# MiniSumoMotors.net
KiCad netlist of a schematic drawn in EAGLE
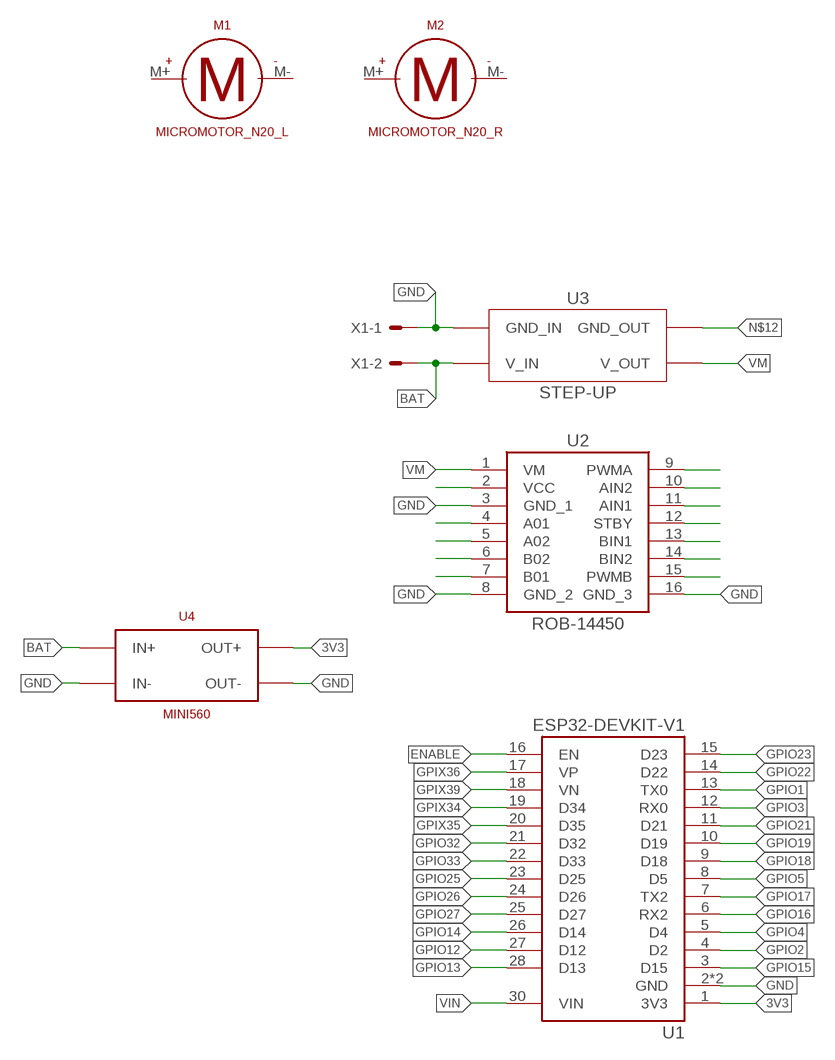
[diagram p0: schematic, sheet 1]

(export (version "E")
  (design (tool "Eeschema 10.0.6"))
  (components
    (comp (ref "M1")
      (value "MICROMOTOR_N20_L")
      (footprint "eagle-import:MICROMOTOR-L")
      (libsource (lib "eagle-import") (part "MICROMOTOR_N20_L"))
    )
    (comp (ref "M2")
      (value "MICROMOTOR_N20_R")
      (footprint "eagle-import:MICROMOTOR-R")
      (libsource (lib "eagle-import") (part "MICROMOTOR_N20_R"))
    )
    (comp (ref "U1")
      (value "ESP32-DEVKIT-V1")
      (footprint "eagle-import:MODULE_ESP32_DEVKIT_V1")
      (fields (field (name "MF") "Do it"))
      (libsource (lib "eagle-import") (part "ESP32-DEVKIT-V1"))
    )
    (comp (ref "U2")
      (value "ROB-14450")
      (footprint "eagle-import:ROB14450")
      (fields (field (name "MOUSER_PART_NUMBER") "474-ROB-14450"))
      (libsource (lib "eagle-import") (part "ROB-14450"))
    )
    (comp (ref "U3")
      (value "STEP-UP")
      (footprint "eagle-import:STEP-UP")
      (libsource (lib "eagle-import") (part "STEP-UP"))
    )
    (comp (ref "U4")
      (value "MINI560")
      (footprint "eagle-import:MINI560")
      (libsource (lib "eagle-import") (part "MINI560"))
    )
    (comp (ref "X1")
      (value "22-23-2021")
      (footprint "eagle-import:22-23-2021")
      (fields (field (name "MF") "MOLEX"))
      (libsource (lib "eagle-import") (part "22-23-2021"))
    )
  )
  (nets
    (net (code "1") (name "3V3") (class "Default")
      (node (ref "U1") (pin "1") (pinfunction "3V3_1") (pintype "output"))
      (node (ref "U4") (pin "P$11") (pinfunction "OUT+_P$11") (pintype "bidirectional"))
      (node (ref "U4") (pin "P$12") (pinfunction "OUT+_P$12") (pintype "bidirectional"))
      (node (ref "U4") (pin "P$15") (pinfunction "OUT+_P$15") (pintype "bidirectional"))
      (node (ref "U4") (pin "P$16") (pinfunction "OUT+_P$16") (pintype "bidirectional"))
    )
    (net (code "2") (name "BAT") (class "Default")
      (node (ref "U3") (pin "V_IN") (pinfunction "V_IN_V_IN") (pintype "bidirectional"))
      (node (ref "U4") (pin "P$3") (pinfunction "IN+_P$3") (pintype "bidirectional"))
      (node (ref "U4") (pin "P$4") (pinfunction "IN+_P$4") (pintype "bidirectional"))
      (node (ref "U4") (pin "P$7") (pinfunction "IN+_P$7") (pintype "bidirectional"))
      (node (ref "U4") (pin "P$8") (pinfunction "IN+_P$8") (pintype "bidirectional"))
      (node (ref "X1") (pin "2") (pinfunction "S_2") (pintype "passive"))
    )
    (net (code "3") (name "ENABLE") (class "Default")
      (node (ref "U1") (pin "16") (pinfunction "EN_16") (pintype "input"))
    )
    (net (code "4") (name "GND") (class "Default")
      (node (ref "U1") (pin "2") (pinfunction "GND_2") (pintype "power_in"))
      (node (ref "U1") (pin "29") (pinfunction "GND_29") (pintype "power_in"))
      (node (ref "U2") (pin "16") (pinfunction "GND_3_16") (pintype "bidirectional"))
      (node (ref "U2") (pin "3") (pinfunction "GND_1_3") (pintype "bidirectional"))
      (node (ref "U2") (pin "8") (pinfunction "GND_2_8") (pintype "bidirectional"))
      (node (ref "U3") (pin "GND_IN") (pinfunction "GND_IN_GND_IN") (pintype "bidirectional"))
      (node (ref "U4") (pin "P$1") (pinfunction "IN-_P$1") (pintype "bidirectional"))
      (node (ref "U4") (pin "P$10") (pinfunction "OUT-_P$10") (pintype "bidirectional"))
      (node (ref "U4") (pin "P$13") (pinfunction "OUT-_P$13") (pintype "bidirectional"))
      (node (ref "U4") (pin "P$14") (pinfunction "OUT-_P$14") (pintype "bidirectional"))
      (node (ref "U4") (pin "P$2") (pinfunction "IN-_P$2") (pintype "bidirectional"))
      (node (ref "U4") (pin "P$5") (pinfunction "IN-_P$5") (pintype "bidirectional"))
      (node (ref "U4") (pin "P$6") (pinfunction "IN-_P$6") (pintype "bidirectional"))
      (node (ref "U4") (pin "P$9") (pinfunction "OUT-_P$9") (pintype "bidirectional"))
      (node (ref "X1") (pin "1") (pinfunction "S_1") (pintype "passive"))
    )
    (net (code "5") (name "GPIO1") (class "Default")
      (node (ref "U1") (pin "13") (pinfunction "TX0_13") (pintype "output"))
    )
    (net (code "6") (name "GPIO2") (class "Default")
      (node (ref "U1") (pin "4") (pinfunction "D2_4") (pintype "bidirectional"))
    )
    (net (code "7") (name "GPIO3") (class "Default")
      (node (ref "U1") (pin "12") (pinfunction "RX0_12") (pintype "input"))
    )
    (net (code "8") (name "GPIO4") (class "Default")
      (node (ref "U1") (pin "5") (pinfunction "D4_5") (pintype "bidirectional"))
    )
    (net (code "9") (name "GPIO5") (class "Default")
      (node (ref "U1") (pin "8") (pinfunction "D5_8") (pintype "bidirectional"))
    )
    (net (code "10") (name "GPIO12") (class "Default")
      (node (ref "U1") (pin "27") (pinfunction "D12_27") (pintype "bidirectional"))
    )
    (net (code "11") (name "GPIO13") (class "Default")
      (node (ref "U1") (pin "28") (pinfunction "D13_28") (pintype "bidirectional"))
    )
    (net (code "12") (name "GPIO14") (class "Default")
      (node (ref "U1") (pin "26") (pinfunction "D14_26") (pintype "bidirectional"))
    )
    (net (code "13") (name "GPIO15") (class "Default")
      (node (ref "U1") (pin "3") (pinfunction "D15_3") (pintype "bidirectional"))
    )
    (net (code "14") (name "GPIO16") (class "Default")
      (node (ref "U1") (pin "6") (pinfunction "RX2_6") (pintype "input"))
    )
    (net (code "15") (name "GPIO17") (class "Default")
      (node (ref "U1") (pin "7") (pinfunction "TX2_7") (pintype "output"))
    )
    (net (code "16") (name "GPIO18") (class "Default")
      (node (ref "U1") (pin "9") (pinfunction "D18_9") (pintype "bidirectional"))
    )
    (net (code "17") (name "GPIO19") (class "Default")
      (node (ref "U1") (pin "10") (pinfunction "D19_10") (pintype "bidirectional"))
    )
    (net (code "18") (name "GPIO21") (class "Default")
      (node (ref "U1") (pin "11") (pinfunction "D21_11") (pintype "bidirectional"))
    )
    (net (code "19") (name "GPIO22") (class "Default")
      (node (ref "U1") (pin "14") (pinfunction "D22_14") (pintype "bidirectional"))
    )
    (net (code "20") (name "GPIO23") (class "Default")
      (node (ref "U1") (pin "15") (pinfunction "D23_15") (pintype "bidirectional"))
    )
    (net (code "21") (name "GPIO25") (class "Default")
      (node (ref "U1") (pin "23") (pinfunction "D25_23") (pintype "bidirectional"))
    )
    (net (code "22") (name "GPIO26") (class "Default")
      (node (ref "U1") (pin "24") (pinfunction "D26_24") (pintype "bidirectional"))
    )
    (net (code "23") (name "GPIO27") (class "Default")
      (node (ref "U1") (pin "25") (pinfunction "D27_25") (pintype "bidirectional"))
    )
    (net (code "24") (name "GPIO32") (class "Default")
      (node (ref "U1") (pin "21") (pinfunction "D32_21") (pintype "bidirectional"))
    )
    (net (code "25") (name "GPIO33") (class "Default")
      (node (ref "U1") (pin "22") (pinfunction "D33_22") (pintype "bidirectional"))
    )
    (net (code "26") (name "GPIX34") (class "Default")
      (node (ref "U1") (pin "19") (pinfunction "D34_19") (pintype "bidirectional"))
    )
    (net (code "27") (name "GPIX35") (class "Default")
      (node (ref "U1") (pin "20") (pinfunction "D35_20") (pintype "bidirectional"))
    )
    (net (code "28") (name "GPIX36") (class "Default")
      (node (ref "U1") (pin "17") (pinfunction "VP_17") (pintype "bidirectional"))
    )
    (net (code "29") (name "GPIX39") (class "Default")
      (node (ref "U1") (pin "18") (pinfunction "VN_18") (pintype "bidirectional"))
    )
    (net (code "30") (name "N$12") (class "Default")
      (node (ref "U3") (pin "GND_OUT") (pinfunction "GND_OUT_GND_OUT") (pintype "bidirectional"))
    )
    (net (code "31") (name "VIN") (class "Default")
      (node (ref "U1") (pin "30") (pinfunction "VIN_30") (pintype "input"))
    )
    (net (code "32") (name "VM") (class "Default")
      (node (ref "U2") (pin "1") (pinfunction "VM_1") (pintype "bidirectional"))
      (node (ref "U3") (pin "V_OUT") (pinfunction "V_OUT_V_OUT") (pintype "bidirectional"))
    )
    (net (code "33") (name "unconnected-(M1-PadM+)") (class "Default")
      (node (ref "M1") (pin "M+") (pinfunction "M+_M+") (pintype "bidirectional"))
    )
    (net (code "34") (name "unconnected-(M1-PadM-)") (class "Default")
      (node (ref "M1") (pin "M-") (pinfunction "M-_M-") (pintype "bidirectional"))
    )
    (net (code "35") (name "unconnected-(M2-PadM+)") (class "Default")
      (node (ref "M2") (pin "M+") (pinfunction "M+_M+") (pintype "bidirectional"))
    )
    (net (code "36") (name "unconnected-(M2-PadM-)") (class "Default")
      (node (ref "M2") (pin "M-") (pinfunction "M-_M-") (pintype "bidirectional"))
    )
    (net (code "37") (name "unconnected-(U2-A01-Pad4)") (class "Default")
      (node (ref "U2") (pin "4") (pinfunction "A01_4") (pintype "bidirectional"))
    )
    (net (code "38") (name "unconnected-(U2-A02-Pad5)") (class "Default")
      (node (ref "U2") (pin "5") (pinfunction "A02_5") (pintype "bidirectional"))
    )
    (net (code "39") (name "unconnected-(U2-AIN1-Pad11)") (class "Default")
      (node (ref "U2") (pin "11") (pinfunction "AIN1_11") (pintype "bidirectional"))
    )
    (net (code "40") (name "unconnected-(U2-AIN2-Pad10)") (class "Default")
      (node (ref "U2") (pin "10") (pinfunction "AIN2_10") (pintype "bidirectional"))
    )
    (net (code "41") (name "unconnected-(U2-B01-Pad7)") (class "Default")
      (node (ref "U2") (pin "7") (pinfunction "B01_7") (pintype "bidirectional"))
    )
    (net (code "42") (name "unconnected-(U2-B02-Pad6)") (class "Default")
      (node (ref "U2") (pin "6") (pinfunction "B02_6") (pintype "bidirectional"))
    )
    (net (code "43") (name "unconnected-(U2-BIN1-Pad13)") (class "Default")
      (node (ref "U2") (pin "13") (pinfunction "BIN1_13") (pintype "bidirectional"))
    )
    (net (code "44") (name "unconnected-(U2-BIN2-Pad14)") (class "Default")
      (node (ref "U2") (pin "14") (pinfunction "BIN2_14") (pintype "bidirectional"))
    )
    (net (code "45") (name "unconnected-(U2-PWMA-Pad9)") (class "Default")
      (node (ref "U2") (pin "9") (pinfunction "PWMA_9") (pintype "bidirectional"))
    )
    (net (code "46") (name "unconnected-(U2-PWMB-Pad15)") (class "Default")
      (node (ref "U2") (pin "15") (pinfunction "PWMB_15") (pintype "bidirectional"))
    )
    (net (code "47") (name "unconnected-(U2-STBY-Pad12)") (class "Default")
      (node (ref "U2") (pin "12") (pinfunction "STBY_12") (pintype "bidirectional"))
    )
    (net (code "48") (name "unconnected-(U2-VCC-Pad2)") (class "Default")
      (node (ref "U2") (pin "2") (pinfunction "VCC_2") (pintype "bidirectional"))
    )
  )
)
